# CoreBoard.net
KiCad netlist of a schematic drawn in Altium Designer
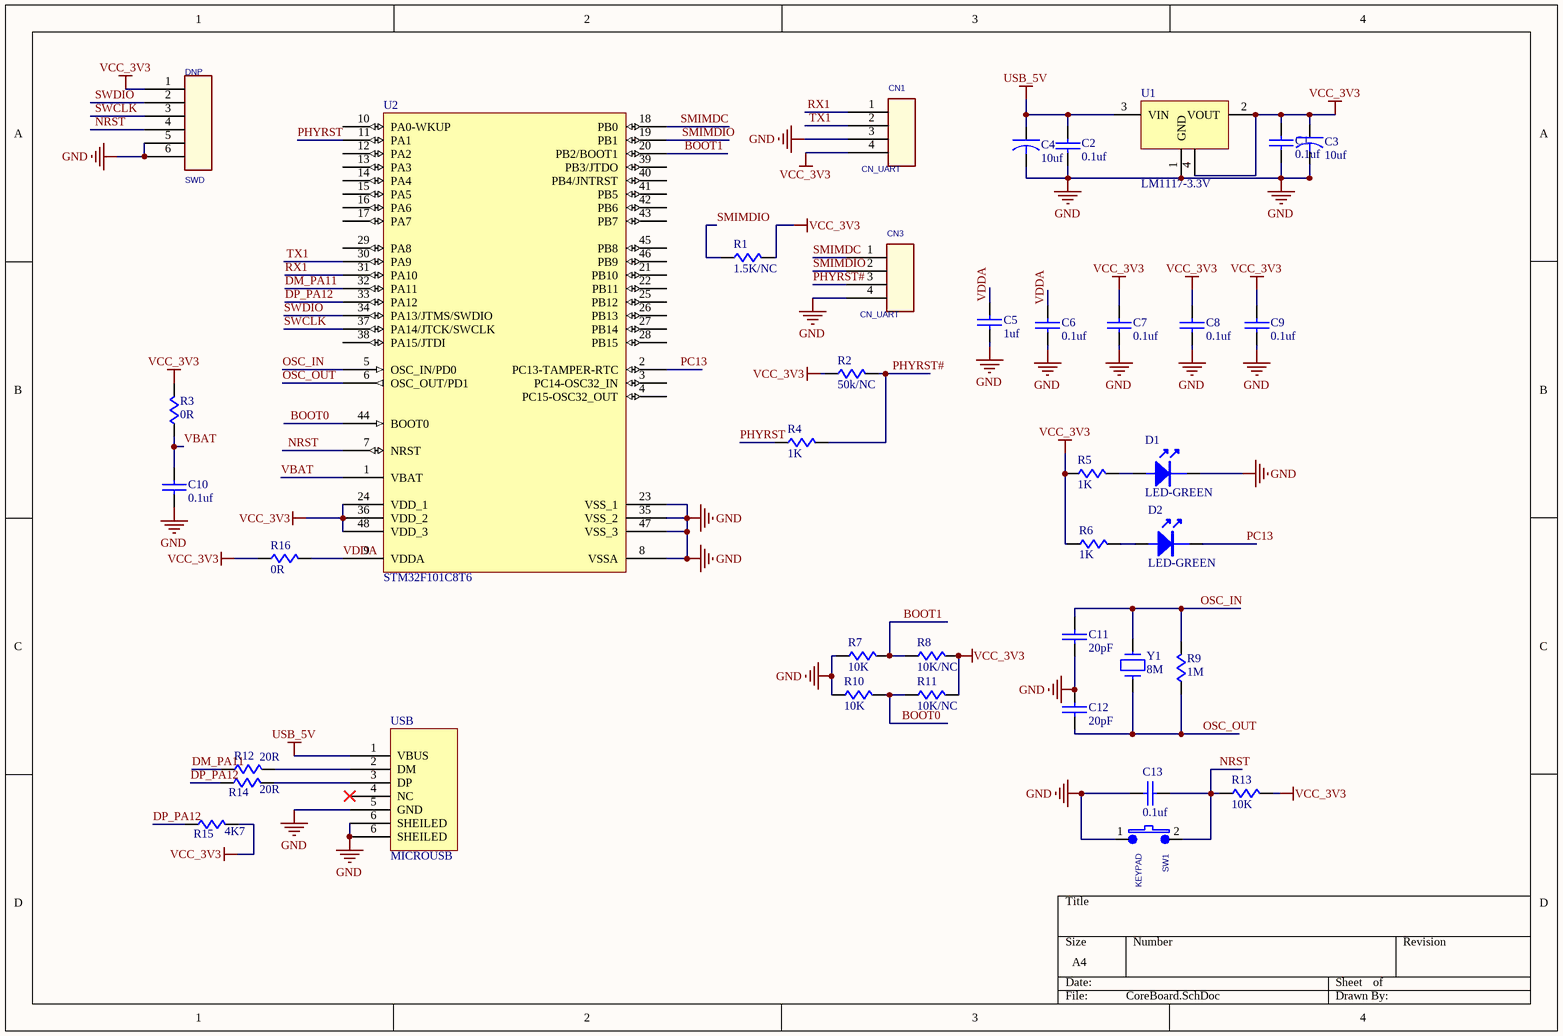
[diagram p0: CoreBoard.SchDoc]

(export (version "E")
  (design (tool "Eeschema 10.0.6"))
  (components
    (comp (ref "C1")
      (value "0.1uf")
      (footprint "C0603")
      (description "Capacitor")
      (libsource (lib "PC JACK") (part "CAP_1"))
    )
    (comp (ref "C2")
      (value "0.1uf")
      (footprint "C0603")
      (description "Capacitor")
      (libsource (lib "PC JACK") (part "CAP_1"))
    )
    (comp (ref "C3")
      (value "10uf")
      (footprint "SMD-CT-2012")
      (description "Capacitor")
      (libsource (lib "PC JACK") (part "CAPACITOR"))
    )
    (comp (ref "C4")
      (value "10uf")
      (footprint "SMD-CT-2012")
      (description "Capacitor")
      (libsource (lib "PC JACK") (part "CAPACITOR"))
    )
    (comp (ref "C5")
      (value "1uf")
      (footprint "C0603")
      (description "Capacitor")
      (libsource (lib "PC JACK") (part "CAP_1"))
    )
    (comp (ref "C6")
      (value "0.1uf")
      (footprint "C0603")
      (description "Capacitor")
      (libsource (lib "PC JACK") (part "CAP_1"))
    )
    (comp (ref "C7")
      (value "0.1uf")
      (footprint "C0603")
      (description "Capacitor")
      (libsource (lib "PC JACK") (part "CAP_1"))
    )
    (comp (ref "C8")
      (value "0.1uf")
      (footprint "C0603")
      (description "Capacitor")
      (libsource (lib "PC JACK") (part "CAP_1"))
    )
    (comp (ref "C9")
      (value "0.1uf")
      (footprint "C0603")
      (description "Capacitor")
      (libsource (lib "PC JACK") (part "CAP_1"))
    )
    (comp (ref "C10")
      (value "0.1uf")
      (footprint "C0603")
      (description "Capacitor")
      (libsource (lib "PC JACK") (part "CAP_1"))
    )
    (comp (ref "C11")
      (value "20pF")
      (footprint "C0603")
      (description "Capacitor")
      (libsource (lib "PC JACK") (part "CAP"))
    )
    (comp (ref "C12")
      (value "20pF")
      (footprint "C0603")
      (description "Capacitor")
      (libsource (lib "PC JACK") (part "CAP"))
    )
    (comp (ref "C13")
      (value "0.1uf")
      (footprint "C0603")
      (description "Capacitor")
      (libsource (lib "PC JACK") (part "CAP_1"))
    )
    (comp (ref "CN1") (value "CN_UART") (libsource (lib "A20_DVK1_BASE_V16_V162") (part "CON4")))
    (comp (ref "CN3") (value "CN_UART") (libsource (lib "A20_DVK1_BASE_V16_V162") (part "CON4")))
    (comp (ref "D1") (value "LED-GREEN") (footprint "LED-0805") (libsource (lib "PC JACK") (part "LED")))
    (comp (ref "D2") (value "LED-GREEN") (footprint "LED-0805") (libsource (lib "PC JACK") (part "LED")))
    (comp (ref "R1") (value "1.5K/NC") (footprint "R0603") (libsource (lib "PC JACK") (part "RES1")))
    (comp (ref "R2") (value "50k/NC") (footprint "R0603") (libsource (lib "PC JACK") (part "RES1")))
    (comp (ref "R3") (value "0R") (footprint "R0603") (libsource (lib "PC JACK") (part "RES1")))
    (comp (ref "R4") (value "1K") (footprint "R0603") (libsource (lib "PC JACK") (part "RES1")))
    (comp (ref "R5") (value "1K") (footprint "R0603") (libsource (lib "PC JACK") (part "RES1")))
    (comp (ref "R6") (value "1K") (footprint "R0603") (libsource (lib "PC JACK") (part "RES1")))
    (comp (ref "R7") (value "10K") (footprint "R0603") (libsource (lib "PC JACK") (part "RES1")))
    (comp (ref "R8") (value "10K/NC") (footprint "R0603") (libsource (lib "PC JACK") (part "RES1")))
    (comp (ref "R9") (value "1M") (footprint "R0603") (libsource (lib "PC JACK") (part "RES1")))
    (comp (ref "R10") (value "10K") (footprint "R0603") (libsource (lib "PC JACK") (part "RES1")))
    (comp (ref "R11") (value "10K/NC") (footprint "R0603") (libsource (lib "PC JACK") (part "RES1")))
    (comp (ref "R12") (value "20R") (footprint "R0603") (libsource (lib "PC JACK") (part "RES1")))
    (comp (ref "R13") (value "10K") (footprint "R0603") (libsource (lib "PC JACK") (part "RES1")))
    (comp (ref "R14") (value "20R") (footprint "R0603") (libsource (lib "PC JACK") (part "RES1")))
    (comp (ref "R15") (value "4K7") (footprint "R0603") (libsource (lib "PC JACK") (part "RES1")))
    (comp (ref "R16") (value "0R") (footprint "R0603") (libsource (lib "PC JACK") (part "RES1")))
    (comp (ref "SW1")
      (value "KEYPAD")
      (libsource (lib "A20_DVK1_BASE_V16_V162") (part "PUSHBUTTON_TSKB-2L_0"))
    )
    (comp (ref "SWD") (value "DNP") (libsource (lib "A20_DVK1_BASE_V16_V162") (part "CON6")))
    (comp (ref "U1") (value "LM1117-3.3V") (footprint "SOT-223") (libsource (lib "PC JACK") (part "LM1117")))
    (comp (ref "U2")
      (value "STM32F101C8T6")
      (footprint "LQFP48_N")
      (description "STM32 ARM-based 32-bit MCU with 64 Kbytes Flash, 48-pin LQFP, Industrial Temperature")
      (fields (field (name "PUBLISHER") "*"))
      (libsource (lib "ST Microcontroller 32-Bit STM32 SCH") (part "STM32F101C8T6"))
    )
    (comp (ref "USB")
      (value "MICROUSB")
      (footprint "PcbLib1:MICRO-USB")
      (libsource (lib "PC JACK") (part "MICROUSB"))
    )
    (comp (ref "Y1")
      (value "8M")
      (footprint "5032-2P")
      (description "Crystal")
      (libsource (lib "PC JACK") (part "CRYSTAL"))
    )
  )
  (nets
    (net (code "1") (name "/BOOT0") (class "Default")
      (node (ref "R10") (pin "2") (pinfunction "2_2") (pintype "passive"))
      (node (ref "R11") (pin "1") (pinfunction "1_1") (pintype "passive"))
      (node (ref "U2") (pin "44") (pinfunction "BOOT0_44") (pintype "input"))
    )
    (net (code "2") (name "/BOOT1") (class "Default")
      (node (ref "R7") (pin "2") (pinfunction "2_2") (pintype "passive"))
      (node (ref "R8") (pin "1") (pinfunction "1_1") (pintype "passive"))
      (node (ref "U2") (pin "20") (pinfunction "PB2/BOOT1_20") (pintype "bidirectional"))
    )
    (net (code "3") (name "/DM_PA11") (class "Default")
      (node (ref "R12") (pin "1") (pinfunction "1_1") (pintype "passive"))
      (node (ref "U2") (pin "32") (pinfunction "PA11_32") (pintype "bidirectional"))
    )
    (net (code "4") (name "/DP_PA12") (class "Default")
      (node (ref "R14") (pin "1") (pinfunction "1_1") (pintype "passive"))
      (node (ref "R15") (pin "1") (pinfunction "1_1") (pintype "passive"))
      (node (ref "U2") (pin "33") (pinfunction "PA12_33") (pintype "bidirectional"))
    )
    (net (code "5") (name "/NRST") (class "Default")
      (node (ref "C13") (pin "2") (pinfunction "2_2") (pintype "passive"))
      (node (ref "R13") (pin "1") (pinfunction "1_1") (pintype "passive"))
      (node (ref "SW1") (pin "2") (pinfunction "2_2") (pintype "passive"))
      (node (ref "SWD") (pin "4") (pinfunction "4_4") (pintype "passive"))
      (node (ref "U2") (pin "7") (pinfunction "NRST_7") (pintype "bidirectional"))
    )
    (net (code "6") (name "/OSC_IN") (class "Default")
      (node (ref "C11") (pin "1") (pinfunction "1_1") (pintype "passive"))
      (node (ref "R9") (pin "2") (pinfunction "2_2") (pintype "passive"))
      (node (ref "U2") (pin "5") (pinfunction "OSC_IN/PD0_5") (pintype "input"))
      (node (ref "Y1") (pin "2") (pinfunction "2_2") (pintype "passive"))
    )
    (net (code "7") (name "/OSC_OUT") (class "Default")
      (node (ref "C12") (pin "2") (pinfunction "2_2") (pintype "passive"))
      (node (ref "R9") (pin "1") (pinfunction "1_1") (pintype "passive"))
      (node (ref "U2") (pin "6") (pinfunction "OSC_OUT/PD1_6") (pintype "output"))
      (node (ref "Y1") (pin "1") (pinfunction "1_1") (pintype "passive"))
    )
    (net (code "8") (name "/PC13") (class "Default")
      (node (ref "D2") (pin "1") (pinfunction "1_1") (pintype "passive"))
      (node (ref "U2") (pin "2") (pinfunction "PC13-TAMPER-RTC_2") (pintype "bidirectional"))
    )
    (net (code "9") (name "/PHYRST") (class "Default")
      (node (ref "R4") (pin "1") (pinfunction "1_1") (pintype "passive"))
      (node (ref "U2") (pin "11") (pinfunction "PA1_11") (pintype "bidirectional"))
    )
    (net (code "10") (name "/PHYRST#") (class "Default")
      (node (ref "CN3") (pin "3") (pinfunction "3_3") (pintype "passive"))
      (node (ref "R2") (pin "2") (pinfunction "2_2") (pintype "passive"))
      (node (ref "R4") (pin "2") (pinfunction "2_2") (pintype "passive"))
    )
    (net (code "11") (name "/RX1") (class "Default")
      (node (ref "CN1") (pin "1") (pinfunction "1_1") (pintype "passive"))
      (node (ref "U2") (pin "31") (pinfunction "PA10_31") (pintype "bidirectional"))
    )
    (net (code "12") (name "/SMIMDC") (class "Default")
      (node (ref "CN3") (pin "1") (pinfunction "1_1") (pintype "passive"))
      (node (ref "U2") (pin "18") (pinfunction "PB0_18") (pintype "bidirectional"))
    )
    (net (code "13") (name "/SMIMDIO") (class "Default")
      (node (ref "CN3") (pin "2") (pinfunction "2_2") (pintype "passive"))
      (node (ref "R1") (pin "1") (pinfunction "1_1") (pintype "passive"))
      (node (ref "U2") (pin "19") (pinfunction "PB1_19") (pintype "bidirectional"))
    )
    (net (code "14") (name "/SWCLK") (class "Default")
      (node (ref "SWD") (pin "3") (pinfunction "3_3") (pintype "passive"))
      (node (ref "U2") (pin "37") (pinfunction "PA14/JTCK/SWCLK_37") (pintype "bidirectional"))
    )
    (net (code "15") (name "/SWDIO") (class "Default")
      (node (ref "SWD") (pin "2") (pinfunction "2_2") (pintype "passive"))
      (node (ref "U2") (pin "34") (pinfunction "PA13/JTMS/SWDIO_34") (pintype "bidirectional"))
    )
    (net (code "16") (name "/TX1") (class "Default")
      (node (ref "CN1") (pin "2") (pinfunction "2_2") (pintype "passive"))
      (node (ref "U2") (pin "30") (pinfunction "PA9_30") (pintype "bidirectional"))
    )
    (net (code "17") (name "/VBAT") (class "Default")
      (node (ref "C10") (pin "1") (pinfunction "1_1") (pintype "passive"))
      (node (ref "R3") (pin "1") (pinfunction "1_1") (pintype "passive"))
      (node (ref "U2") (pin "1") (pinfunction "VBAT_1") (pintype "power_in"))
    )
    (net (code "18") (name "/VDDA") (class "Default")
      (node (ref "C5") (pin "1") (pinfunction "1_1") (pintype "passive"))
      (node (ref "C6") (pin "1") (pinfunction "1_1") (pintype "passive"))
      (node (ref "R16") (pin "2") (pinfunction "2_2") (pintype "passive"))
      (node (ref "U2") (pin "9") (pinfunction "VDDA_9") (pintype "power_in"))
    )
    (net (code "19") (name "GND") (class "Default")
      (node (ref "C1") (pin "2") (pinfunction "2_2") (pintype "passive"))
      (node (ref "C10") (pin "2") (pinfunction "2_2") (pintype "passive"))
      (node (ref "C11") (pin "2") (pinfunction "2_2") (pintype "passive"))
      (node (ref "C12") (pin "1") (pinfunction "1_1") (pintype "passive"))
      (node (ref "C13") (pin "1") (pinfunction "1_1") (pintype "passive"))
      (node (ref "C2") (pin "2") (pinfunction "2_2") (pintype "passive"))
      (node (ref "C3") (pin "2") (pinfunction "2_2") (pintype "passive"))
      (node (ref "C4") (pin "2") (pinfunction "2_2") (pintype "passive"))
      (node (ref "C5") (pin "2") (pinfunction "2_2") (pintype "passive"))
      (node (ref "C6") (pin "2") (pinfunction "2_2") (pintype "passive"))
      (node (ref "C7") (pin "2") (pinfunction "2_2") (pintype "passive"))
      (node (ref "C8") (pin "2") (pinfunction "2_2") (pintype "passive"))
      (node (ref "C9") (pin "2") (pinfunction "2_2") (pintype "passive"))
      (node (ref "CN1") (pin "3") (pinfunction "3_3") (pintype "passive"))
      (node (ref "CN3") (pin "4") (pinfunction "4_4") (pintype "passive"))
      (node (ref "D1") (pin "1") (pinfunction "1_1") (pintype "passive"))
      (node (ref "R10") (pin "1") (pinfunction "1_1") (pintype "passive"))
      (node (ref "R7") (pin "1") (pinfunction "1_1") (pintype "passive"))
      (node (ref "SW1") (pin "1") (pinfunction "1_1") (pintype "passive"))
      (node (ref "SWD") (pin "5") (pinfunction "5_5") (pintype "passive"))
      (node (ref "SWD") (pin "6") (pinfunction "6_6") (pintype "passive"))
      (node (ref "U1") (pin "1") (pinfunction "GND_1") (pintype "passive"))
      (node (ref "U2") (pin "23") (pinfunction "VSS_1_23") (pintype "power_in"))
      (node (ref "U2") (pin "35") (pinfunction "VSS_2_35") (pintype "power_in"))
      (node (ref "U2") (pin "47") (pinfunction "VSS_3_47") (pintype "power_in"))
      (node (ref "U2") (pin "8") (pinfunction "VSSA_8") (pintype "power_in"))
      (node (ref "USB") (pin "5") (pinfunction "GND_5") (pintype "passive"))
      (node (ref "USB") (pin "6") (pinfunction "SHEILED_6") (pintype "passive"))
    )
    (net (code "20") (name "Net-(D1-Pad2)") (class "Default")
      (node (ref "D1") (pin "2") (pinfunction "2_2") (pintype "passive"))
      (node (ref "R5") (pin "2") (pinfunction "2_2") (pintype "passive"))
    )
    (net (code "21") (name "Net-(D2-Pad2)") (class "Default")
      (node (ref "D2") (pin "2") (pinfunction "2_2") (pintype "passive"))
      (node (ref "R6") (pin "2") (pinfunction "2_2") (pintype "passive"))
    )
    (net (code "22") (name "Net-(USB-DM)") (class "Default")
      (node (ref "R12") (pin "2") (pinfunction "2_2") (pintype "passive"))
      (node (ref "USB") (pin "2") (pinfunction "DM_2") (pintype "passive"))
    )
    (net (code "23") (name "Net-(USB-DP)") (class "Default")
      (node (ref "R14") (pin "2") (pinfunction "2_2") (pintype "passive"))
      (node (ref "USB") (pin "3") (pinfunction "DP_3") (pintype "passive"))
    )
    (net (code "24") (name "USB_5V") (class "Default")
      (node (ref "C2") (pin "1") (pinfunction "1_1") (pintype "passive"))
      (node (ref "C4") (pin "1") (pinfunction "1_1") (pintype "passive"))
      (node (ref "U1") (pin "3") (pinfunction "VIN_3") (pintype "passive"))
      (node (ref "USB") (pin "1") (pinfunction "VBUS_1") (pintype "passive"))
    )
    (net (code "25") (name "VCC_3V3") (class "Default")
      (node (ref "C1") (pin "1") (pinfunction "1_1") (pintype "passive"))
      (node (ref "C3") (pin "1") (pinfunction "1_1") (pintype "passive"))
      (node (ref "C7") (pin "1") (pinfunction "1_1") (pintype "passive"))
      (node (ref "C8") (pin "1") (pinfunction "1_1") (pintype "passive"))
      (node (ref "C9") (pin "1") (pinfunction "1_1") (pintype "passive"))
      (node (ref "CN1") (pin "4") (pinfunction "4_4") (pintype "passive"))
      (node (ref "R1") (pin "2") (pinfunction "2_2") (pintype "passive"))
      (node (ref "R11") (pin "2") (pinfunction "2_2") (pintype "passive"))
      (node (ref "R13") (pin "2") (pinfunction "2_2") (pintype "passive"))
      (node (ref "R15") (pin "2") (pinfunction "2_2") (pintype "passive"))
      (node (ref "R16") (pin "1") (pinfunction "1_1") (pintype "passive"))
      (node (ref "R2") (pin "1") (pinfunction "1_1") (pintype "passive"))
      (node (ref "R3") (pin "2") (pinfunction "2_2") (pintype "passive"))
      (node (ref "R5") (pin "1") (pinfunction "1_1") (pintype "passive"))
      (node (ref "R6") (pin "1") (pinfunction "1_1") (pintype "passive"))
      (node (ref "R8") (pin "2") (pinfunction "2_2") (pintype "passive"))
      (node (ref "SWD") (pin "1") (pinfunction "1_1") (pintype "passive"))
      (node (ref "U1") (pin "2") (pinfunction "VOUT_2") (pintype "passive"))
      (node (ref "U1") (pin "4") (pintype "passive"))
      (node (ref "U2") (pin "24") (pinfunction "VDD_1_24") (pintype "power_in"))
      (node (ref "U2") (pin "36") (pinfunction "VDD_2_36") (pintype "power_in"))
      (node (ref "U2") (pin "48") (pinfunction "VDD_3_48") (pintype "power_in"))
    )
    (net (code "26") (name "unconnected-(U2-PA0-WKUP-Pad10)") (class "Default")
      (node (ref "U2") (pin "10") (pinfunction "PA0-WKUP_10") (pintype "bidirectional"))
    )
    (net (code "27") (name "unconnected-(U2-PA2-Pad12)") (class "Default")
      (node (ref "U2") (pin "12") (pinfunction "PA2_12") (pintype "bidirectional"))
    )
    (net (code "28") (name "unconnected-(U2-PA3-Pad13)") (class "Default")
      (node (ref "U2") (pin "13") (pinfunction "PA3_13") (pintype "bidirectional"))
    )
    (net (code "29") (name "unconnected-(U2-PA4-Pad14)") (class "Default")
      (node (ref "U2") (pin "14") (pinfunction "PA4_14") (pintype "bidirectional"))
    )
    (net (code "30") (name "unconnected-(U2-PA5-Pad15)") (class "Default")
      (node (ref "U2") (pin "15") (pinfunction "PA5_15") (pintype "bidirectional"))
    )
    (net (code "31") (name "unconnected-(U2-PA6-Pad16)") (class "Default")
      (node (ref "U2") (pin "16") (pinfunction "PA6_16") (pintype "bidirectional"))
    )
    (net (code "32") (name "unconnected-(U2-PA7-Pad17)") (class "Default")
      (node (ref "U2") (pin "17") (pinfunction "PA7_17") (pintype "bidirectional"))
    )
    (net (code "33") (name "unconnected-(U2-PA8-Pad29)") (class "Default")
      (node (ref "U2") (pin "29") (pinfunction "PA8_29") (pintype "bidirectional"))
    )
    (net (code "34") (name "unconnected-(U2-PA15{slash}JTDI-Pad38)") (class "Default")
      (node (ref "U2") (pin "38") (pinfunction "PA15/JTDI_38") (pintype "bidirectional"))
    )
    (net (code "35") (name "unconnected-(U2-PB3{slash}JTDO-Pad39)") (class "Default")
      (node (ref "U2") (pin "39") (pinfunction "PB3/JTDO_39") (pintype "bidirectional"))
    )
    (net (code "36") (name "unconnected-(U2-PB4{slash}JNTRST-Pad40)") (class "Default")
      (node (ref "U2") (pin "40") (pinfunction "PB4/JNTRST_40") (pintype "bidirectional"))
    )
    (net (code "37") (name "unconnected-(U2-PB5-Pad41)") (class "Default")
      (node (ref "U2") (pin "41") (pinfunction "PB5_41") (pintype "bidirectional"))
    )
    (net (code "38") (name "unconnected-(U2-PB6-Pad42)") (class "Default")
      (node (ref "U2") (pin "42") (pinfunction "PB6_42") (pintype "bidirectional"))
    )
    (net (code "39") (name "unconnected-(U2-PB7-Pad43)") (class "Default")
      (node (ref "U2") (pin "43") (pinfunction "PB7_43") (pintype "bidirectional"))
    )
    (net (code "40") (name "unconnected-(U2-PB8-Pad45)") (class "Default")
      (node (ref "U2") (pin "45") (pinfunction "PB8_45") (pintype "bidirectional"))
    )
    (net (code "41") (name "unconnected-(U2-PB9-Pad46)") (class "Default")
      (node (ref "U2") (pin "46") (pinfunction "PB9_46") (pintype "bidirectional"))
    )
    (net (code "42") (name "unconnected-(U2-PB10-Pad21)") (class "Default")
      (node (ref "U2") (pin "21") (pinfunction "PB10_21") (pintype "bidirectional"))
    )
    (net (code "43") (name "unconnected-(U2-PB11-Pad22)") (class "Default")
      (node (ref "U2") (pin "22") (pinfunction "PB11_22") (pintype "bidirectional"))
    )
    (net (code "44") (name "unconnected-(U2-PB12-Pad25)") (class "Default")
      (node (ref "U2") (pin "25") (pinfunction "PB12_25") (pintype "bidirectional"))
    )
    (net (code "45") (name "unconnected-(U2-PB13-Pad26)") (class "Default")
      (node (ref "U2") (pin "26") (pinfunction "PB13_26") (pintype "bidirectional"))
    )
    (net (code "46") (name "unconnected-(U2-PB14-Pad27)") (class "Default")
      (node (ref "U2") (pin "27") (pinfunction "PB14_27") (pintype "bidirectional"))
    )
    (net (code "47") (name "unconnected-(U2-PB15-Pad28)") (class "Default")
      (node (ref "U2") (pin "28") (pinfunction "PB15_28") (pintype "bidirectional"))
    )
    (net (code "48") (name "unconnected-(U2-PC14-OSC32_IN-Pad3)") (class "Default")
      (node (ref "U2") (pin "3") (pinfunction "PC14-OSC32_IN_3") (pintype "bidirectional"))
    )
    (net (code "49") (name "unconnected-(U2-PC15-OSC32_OUT-Pad4)") (class "Default")
      (node (ref "U2") (pin "4") (pinfunction "PC15-OSC32_OUT_4") (pintype "bidirectional"))
    )
    (net (code "50") (name "unconnected-(USB-NC-Pad4)") (class "Default")
      (node (ref "USB") (pin "4") (pinfunction "NC_4") (pintype "passive+no_connect"))
    )
  )
)
